# Power_CH340G.net
KiCad netlist of a schematic drawn in Altium Designer
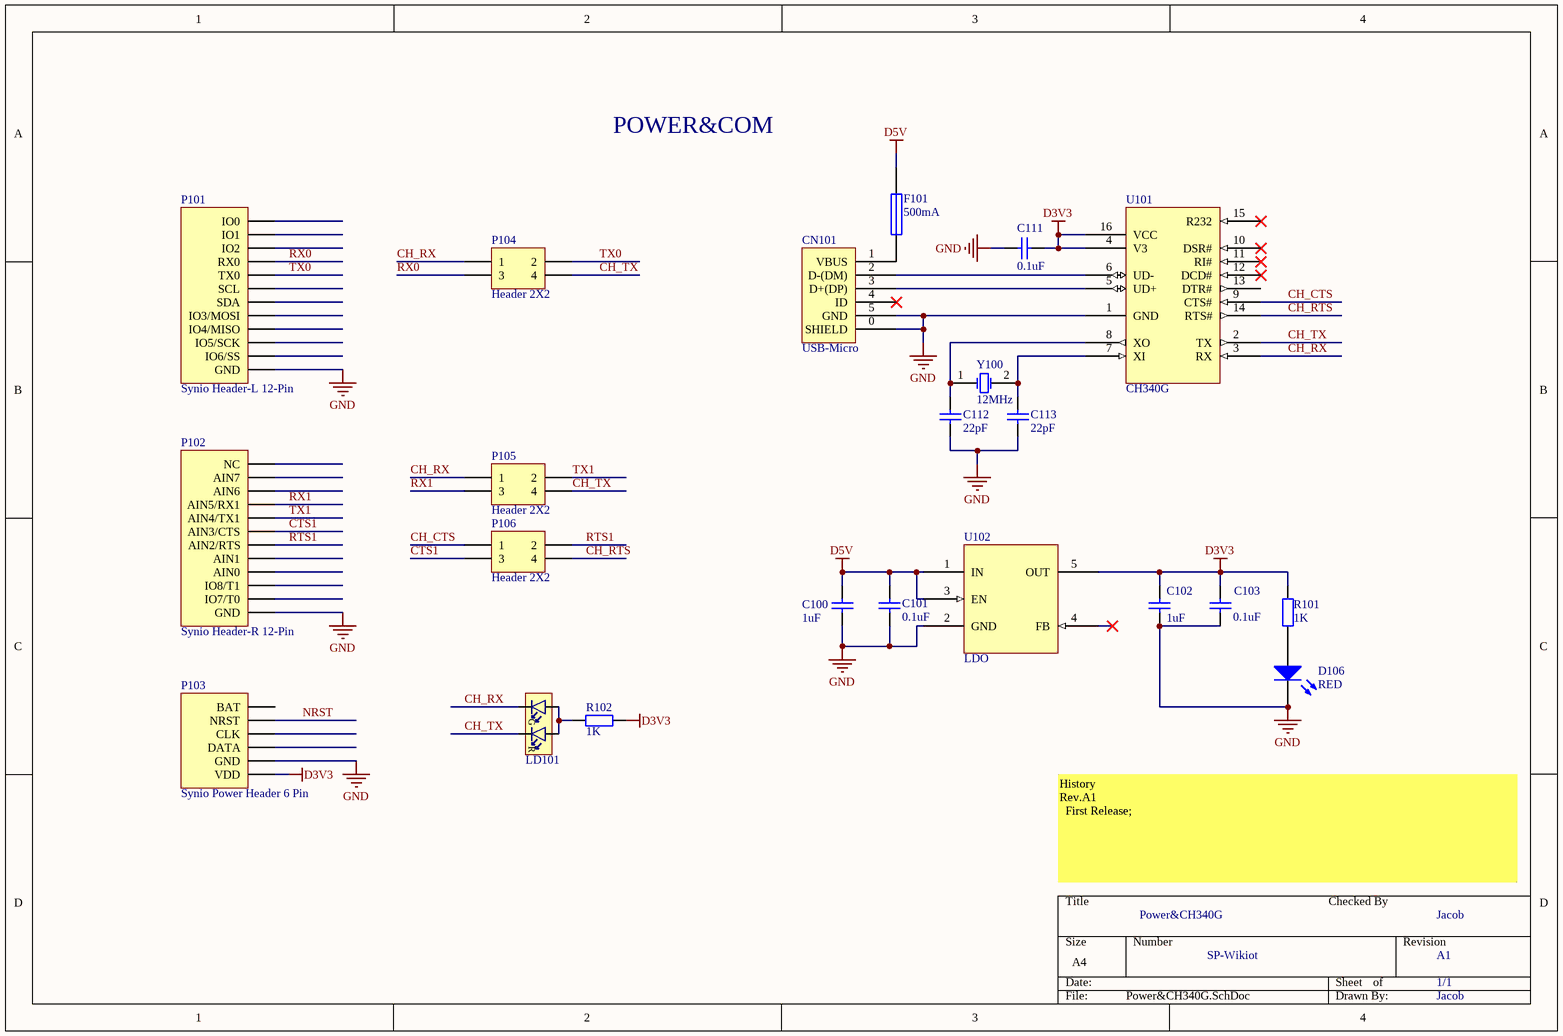
[diagram p0: Power&CH340G.SchDoc]

(export (version "E")
  (design (tool "Eeschema 10.0.6"))
  (components
    (comp (ref "C100")
      (value "1uF")
      (footprint "0603M")
      (description "Capacitor")
      (libsource (lib "Studio") (part "Cap"))
    )
    (comp (ref "C101")
      (value "0.1uF")
      (footprint "0603M")
      (description "Capacitor")
      (libsource (lib "Studio") (part "Cap"))
    )
    (comp (ref "C102")
      (value "1uF")
      (footprint "0603M")
      (description "Capacitor")
      (libsource (lib "Studio") (part "Cap"))
    )
    (comp (ref "C103")
      (value "0.1uF")
      (footprint "0603M")
      (description "Capacitor")
      (libsource (lib "Studio") (part "Cap"))
    )
    (comp (ref "C111")
      (value "0.1uF")
      (footprint "0603M")
      (description "Capacitor")
      (libsource (lib "Studio") (part "Cap"))
    )
    (comp (ref "C112")
      (value "22pF")
      (footprint "0603M")
      (description "Capacitor")
      (fields (field (name "PUBLISHER") "Altium Limited"))
      (libsource (lib "Miscellaneous Devices") (part "Cap"))
    )
    (comp (ref "C113")
      (value "22pF")
      (footprint "0603M")
      (description "Capacitor")
      (fields (field (name "PUBLISHER") "Altium Limited"))
      (libsource (lib "Miscellaneous Devices") (part "Cap"))
    )
    (comp (ref "CN101")
      (value "USB-Micro")
      (footprint "USB-MICRO-Female-Lite")
      (libsource (lib "Connector") (part "USB-Micro"))
    )
    (comp (ref "D106")
      (value "RED")
      (footprint "0603pn")
      (description "Typical INFRARED GaAs LED")
      (fields (field (name "PUBLISHER") "Altium Limited"))
      (libsource (lib "Miscellaneous Devices") (part "LED0"))
    )
    (comp (ref "F101")
      (value "500mA")
      (footprint "0805")
      (description "Fuse")
      (fields (field (name "PUBLISHER") "Altium Limited"))
      (libsource (lib "Studio") (part "Fuse 1"))
    )
    (comp (ref "LD101")
      (value "LTST-C195KGJRKT")
      (footprint "0805-LED-Bi")
      (description "Avago, HSMF-A203 Bi-Color LED")
      (fields
        (field (name "MANUFACTURER") "Lite-On Inc")
        (field (name "2ND SOURCE PART NUMBER") "859-LTST-C195KGJRKT")
        (field (name "PUBLISHER") "Nordic Semiconductor")
      )
      (libsource (lib "Misc") (part "LED-DUAL"))
    )
    (comp (ref "P101")
      (value "Synio Header-L 12-Pin")
      (footprint "HDR1X12")
      (description "Synio Header-L, 12-Pin")
      (fields (field (name "PUBLISHER") "Altium Limited"))
      (libsource (lib "Connector") (part "Synio Header-L 12-Pin"))
    )
    (comp (ref "P102")
      (value "Synio Header-R 12-Pin")
      (footprint "HDR1X12")
      (description "Synio Header-R, 12-Pin")
      (fields (field (name "PUBLISHER") "Altium Limited"))
      (libsource (lib "Connector") (part "Synio Header-R 12-Pin"))
    )
    (comp (ref "P103")
      (value "Synio Power Header 6 Pin")
      (footprint "HDR1X6/2.54MM")
      (libsource (lib "Connector") (part "Synio Power Header 6 Pin"))
    )
    (comp (ref "P104")
      (value "Header 2X2")
      (footprint "HDR2X2/2.54MM")
      (description "Header, 2-Pin, Dual row")
      (fields (field (name "PUBLISHER") "Altium Limited"))
      (libsource (lib "Miscellaneous Connectors") (part "Header 2X2"))
    )
    (comp (ref "P105")
      (value "Header 2X2")
      (footprint "HDR2X2/2.54MM")
      (description "Header, 2-Pin, Dual row")
      (fields (field (name "PUBLISHER") "Altium Limited"))
      (libsource (lib "Miscellaneous Connectors") (part "Header 2X2"))
    )
    (comp (ref "P106")
      (value "Header 2X2")
      (footprint "HDR2X2/2.54MM")
      (description "Header, 2-Pin, Dual row")
      (fields (field (name "PUBLISHER") "Altium Limited"))
      (libsource (lib "Miscellaneous Connectors") (part "Header 2X2"))
    )
    (comp (ref "R101")
      (value "1K")
      (footprint "0603M")
      (description "Resistor")
      (fields (field (name "PUBLISHER") "Altium Limited"))
      (libsource (lib "") (part "Res2_1"))
    )
    (comp (ref "R102")
      (value "1K")
      (footprint "0603M")
      (description "Resistor")
      (fields (field (name "PUBLISHER") "Altium Limited"))
      (libsource (lib "Miscellaneous Devices") (part "Res2"))
    )
    (comp (ref "U101")
      (value "CH340G")
      (footprint "SO16_M")
      (description "USB to UART IC")
      (libsource (lib "Logic") (part "CH340G"))
    )
    (comp (ref "U102")
      (value "LDO")
      (footprint "SOT23-5")
      (description "General LDO SOT23-5")
      (libsource (lib "Power") (part "LDO-SOT23-5"))
    )
    (comp (ref "Y100")
      (value "12MHz")
      (footprint "XTAL_49S")
      (description "Crystal Oscillator")
      (fields (field (name "PUBLISHER") "Altium Limited"))
      (libsource (lib "Miscellaneous Devices") (part "XTAL"))
    )
  )
  (nets
    (net (code "1") (name "/CH_CTS") (class "Default")
      (node (ref "P106") (pin "1") (pinfunction "1_1") (pintype "passive"))
      (node (ref "U101") (pin "9") (pinfunction "CTS#_9") (pintype "input"))
    )
    (net (code "2") (name "/CH_RTS") (class "Default")
      (node (ref "P106") (pin "4") (pinfunction "4_4") (pintype "passive"))
      (node (ref "U101") (pin "14") (pinfunction "RTS#_14") (pintype "output"))
    )
    (net (code "3") (name "/CH_RX") (class "Default")
      (node (ref "LD101") (pin "1") (pinfunction "C1_1") (pintype "passive"))
      (node (ref "P104") (pin "1") (pinfunction "1_1") (pintype "passive"))
      (node (ref "P105") (pin "1") (pinfunction "1_1") (pintype "passive"))
      (node (ref "U101") (pin "3") (pinfunction "RX_3") (pintype "input"))
    )
    (net (code "4") (name "/CH_TX") (class "Default")
      (node (ref "LD101") (pin "2") (pinfunction "C2_2") (pintype "passive"))
      (node (ref "P104") (pin "4") (pinfunction "4_4") (pintype "passive"))
      (node (ref "P105") (pin "4") (pinfunction "4_4") (pintype "passive"))
      (node (ref "U101") (pin "2") (pinfunction "TX_2") (pintype "output"))
    )
    (net (code "5") (name "/CTS1") (class "Default")
      (node (ref "P102") (pin "7") (pinfunction "AIN3/CTS_7") (pintype "passive"))
      (node (ref "P106") (pin "3") (pinfunction "3_3") (pintype "passive"))
    )
    (net (code "6") (name "/NRST") (class "Default")
      (node (ref "P103") (pin "5") (pinfunction "NRST_5") (pintype "passive"))
    )
    (net (code "7") (name "/RTS1") (class "Default")
      (node (ref "P102") (pin "6") (pinfunction "AIN2/RTS_6") (pintype "passive"))
      (node (ref "P106") (pin "2") (pinfunction "2_2") (pintype "passive"))
    )
    (net (code "8") (name "/RX0") (class "Default")
      (node (ref "P101") (pin "9") (pinfunction "RX0_9") (pintype "passive"))
      (node (ref "P104") (pin "3") (pinfunction "3_3") (pintype "passive"))
    )
    (net (code "9") (name "/RX1") (class "Default")
      (node (ref "P102") (pin "9") (pinfunction "AIN5/RX1_9") (pintype "passive"))
      (node (ref "P105") (pin "3") (pinfunction "3_3") (pintype "passive"))
    )
    (net (code "10") (name "/TX0") (class "Default")
      (node (ref "P101") (pin "8") (pinfunction "TX0_8") (pintype "passive"))
      (node (ref "P104") (pin "2") (pinfunction "2_2") (pintype "passive"))
    )
    (net (code "11") (name "/TX1") (class "Default")
      (node (ref "P102") (pin "8") (pinfunction "AIN4/TX1_8") (pintype "passive"))
      (node (ref "P105") (pin "2") (pinfunction "2_2") (pintype "passive"))
    )
    (net (code "12") (name "D3V3") (class "Default")
      (node (ref "C102") (pin "2") (pinfunction "2_2") (pintype "passive"))
      (node (ref "C103") (pin "2") (pinfunction "2_2") (pintype "passive"))
      (node (ref "C111") (pin "2") (pinfunction "2_2") (pintype "passive"))
      (node (ref "P103") (pin "1") (pinfunction "VDD_1") (pintype "passive"))
      (node (ref "R101") (pin "2") (pinfunction "2_2") (pintype "passive"))
      (node (ref "R102") (pin "1") (pinfunction "1_1") (pintype "passive"))
      (node (ref "U101") (pin "16") (pinfunction "VCC_16") (pintype "power_in"))
      (node (ref "U101") (pin "4") (pinfunction "V3_4") (pintype "power_in"))
      (node (ref "U102") (pin "5") (pinfunction "OUT_5") (pintype "power_in"))
    )
    (net (code "13") (name "D5V") (class "Default")
      (node (ref "C100") (pin "2") (pinfunction "2_2") (pintype "passive"))
      (node (ref "C101") (pin "2") (pinfunction "2_2") (pintype "passive"))
      (node (ref "F101") (pin "1") (pinfunction "1_1") (pintype "passive"))
      (node (ref "U102") (pin "1") (pinfunction "IN_1") (pintype "power_in"))
      (node (ref "U102") (pin "3") (pinfunction "EN_3") (pintype "input"))
    )
    (net (code "14") (name "GND") (class "Default")
      (node (ref "C100") (pin "1") (pinfunction "1_1") (pintype "passive"))
      (node (ref "C101") (pin "1") (pinfunction "1_1") (pintype "passive"))
      (node (ref "C102") (pin "1") (pinfunction "1_1") (pintype "passive"))
      (node (ref "C103") (pin "1") (pinfunction "1_1") (pintype "passive"))
      (node (ref "C111") (pin "1") (pinfunction "1_1") (pintype "passive"))
      (node (ref "C112") (pin "1") (pinfunction "1_1") (pintype "passive"))
      (node (ref "C113") (pin "1") (pinfunction "1_1") (pintype "passive"))
      (node (ref "CN101") (pin "0") (pinfunction "SHIELD_0") (pintype "passive"))
      (node (ref "CN101") (pin "5") (pinfunction "GND_5") (pintype "passive"))
      (node (ref "D106") (pin "2") (pinfunction "K_2") (pintype "passive"))
      (node (ref "P101") (pin "1") (pinfunction "GND_1") (pintype "passive"))
      (node (ref "P102") (pin "1") (pinfunction "GND_1") (pintype "passive"))
      (node (ref "P103") (pin "2") (pinfunction "GND_2") (pintype "passive"))
      (node (ref "U101") (pin "1") (pinfunction "GND_1") (pintype "power_in"))
      (node (ref "U102") (pin "2") (pinfunction "GND_2") (pintype "power_in"))
    )
    (net (code "15") (name "Net-(CN101-D+(DP))") (class "Default")
      (node (ref "CN101") (pin "3") (pinfunction "D+(DP)_3") (pintype "passive"))
      (node (ref "U101") (pin "5") (pinfunction "UD+_5") (pintype "bidirectional"))
    )
    (net (code "16") (name "Net-(CN101-D-(DM))") (class "Default")
      (node (ref "CN101") (pin "2") (pinfunction "D-(DM)_2") (pintype "passive"))
      (node (ref "U101") (pin "6") (pinfunction "UD-_6") (pintype "bidirectional"))
    )
    (net (code "17") (name "Net-(CN101-VBUS)") (class "Default")
      (node (ref "CN101") (pin "1") (pinfunction "VBUS_1") (pintype "passive"))
      (node (ref "F101") (pin "2") (pinfunction "2_2") (pintype "passive"))
    )
    (net (code "18") (name "Net-(D106-A)") (class "Default")
      (node (ref "D106") (pin "1") (pinfunction "A_1") (pintype "passive"))
      (node (ref "R101") (pin "1") (pinfunction "1_1") (pintype "passive"))
    )
    (net (code "19") (name "Net-(LD101-A1)") (class "Default")
      (node (ref "LD101") (pin "3") (pinfunction "A2_3") (pintype "passive"))
      (node (ref "LD101") (pin "4") (pinfunction "A1_4") (pintype "passive"))
      (node (ref "R102") (pin "2") (pinfunction "2_2") (pintype "passive"))
    )
    (net (code "20") (name "Net-(U101-XI)") (class "Default")
      (node (ref "C113") (pin "2") (pinfunction "2_2") (pintype "passive"))
      (node (ref "U101") (pin "7") (pinfunction "XI_7") (pintype "input"))
      (node (ref "Y100") (pin "2") (pinfunction "OSC2_2") (pintype "passive"))
    )
    (net (code "21") (name "Net-(U101-XO)") (class "Default")
      (node (ref "C112") (pin "2") (pinfunction "2_2") (pintype "passive"))
      (node (ref "U101") (pin "8") (pinfunction "XO_8") (pintype "output"))
      (node (ref "Y100") (pin "1") (pinfunction "OSC1_1") (pintype "passive"))
    )
    (net (code "22") (name "unconnected-(CN101-ID-Pad4)") (class "Default")
      (node (ref "CN101") (pin "4") (pinfunction "ID_4") (pintype "passive+no_connect"))
    )
    (net (code "23") (name "unconnected-(P101-IO0-Pad12)") (class "Default")
      (node (ref "P101") (pin "12") (pinfunction "IO0_12") (pintype "passive"))
    )
    (net (code "24") (name "unconnected-(P101-IO1-Pad11)") (class "Default")
      (node (ref "P101") (pin "11") (pinfunction "IO1_11") (pintype "passive"))
    )
    (net (code "25") (name "unconnected-(P101-IO2-Pad10)") (class "Default")
      (node (ref "P101") (pin "10") (pinfunction "IO2_10") (pintype "passive"))
    )
    (net (code "26") (name "unconnected-(P101-IO3{slash}MOSI-Pad5)") (class "Default")
      (node (ref "P101") (pin "5") (pinfunction "IO3/MOSI_5") (pintype "passive"))
    )
    (net (code "27") (name "unconnected-(P101-IO4{slash}MISO-Pad4)") (class "Default")
      (node (ref "P101") (pin "4") (pinfunction "IO4/MISO_4") (pintype "passive"))
    )
    (net (code "28") (name "unconnected-(P101-IO5{slash}SCK-Pad3)") (class "Default")
      (node (ref "P101") (pin "3") (pinfunction "IO5/SCK_3") (pintype "passive"))
    )
    (net (code "29") (name "unconnected-(P101-IO6{slash}SS-Pad2)") (class "Default")
      (node (ref "P101") (pin "2") (pinfunction "IO6/SS_2") (pintype "passive"))
    )
    (net (code "30") (name "unconnected-(P101-SCL-Pad7)") (class "Default")
      (node (ref "P101") (pin "7") (pinfunction "SCL_7") (pintype "passive"))
    )
    (net (code "31") (name "unconnected-(P101-SDA-Pad6)") (class "Default")
      (node (ref "P101") (pin "6") (pinfunction "SDA_6") (pintype "passive"))
    )
    (net (code "32") (name "unconnected-(P102-AIN0-Pad4)") (class "Default")
      (node (ref "P102") (pin "4") (pinfunction "AIN0_4") (pintype "passive"))
    )
    (net (code "33") (name "unconnected-(P102-AIN1-Pad5)") (class "Default")
      (node (ref "P102") (pin "5") (pinfunction "AIN1_5") (pintype "passive"))
    )
    (net (code "34") (name "unconnected-(P102-AIN6-Pad10)") (class "Default")
      (node (ref "P102") (pin "10") (pinfunction "AIN6_10") (pintype "passive"))
    )
    (net (code "35") (name "unconnected-(P102-AIN7-Pad11)") (class "Default")
      (node (ref "P102") (pin "11") (pinfunction "AIN7_11") (pintype "passive"))
    )
    (net (code "36") (name "unconnected-(P102-IO7{slash}T0-Pad2)") (class "Default")
      (node (ref "P102") (pin "2") (pinfunction "IO7/T0_2") (pintype "passive"))
    )
    (net (code "37") (name "unconnected-(P102-IO8{slash}T1-Pad3)") (class "Default")
      (node (ref "P102") (pin "3") (pinfunction "IO8/T1_3") (pintype "passive"))
    )
    (net (code "38") (name "unconnected-(P102-NC-Pad12)") (class "Default")
      (node (ref "P102") (pin "12") (pinfunction "NC_12") (pintype "passive"))
    )
    (net (code "39") (name "unconnected-(P103-BAT-Pad6)") (class "Default")
      (node (ref "P103") (pin "6") (pinfunction "BAT_6") (pintype "passive"))
    )
    (net (code "40") (name "unconnected-(P103-CLK-Pad4)") (class "Default")
      (node (ref "P103") (pin "4") (pinfunction "CLK_4") (pintype "passive"))
    )
    (net (code "41") (name "unconnected-(P103-DATA-Pad3)") (class "Default")
      (node (ref "P103") (pin "3") (pinfunction "DATA_3") (pintype "passive"))
    )
    (net (code "42") (name "unconnected-(U101-DCD#-Pad12)") (class "Default")
      (node (ref "U101") (pin "12") (pinfunction "DCD#_12") (pintype "input+no_connect"))
    )
    (net (code "43") (name "unconnected-(U101-DSR#-Pad10)") (class "Default")
      (node (ref "U101") (pin "10") (pinfunction "DSR#_10") (pintype "input+no_connect"))
    )
    (net (code "44") (name "unconnected-(U101-DTR#-Pad13)") (class "Default")
      (node (ref "U101") (pin "13") (pinfunction "DTR#_13") (pintype "output"))
    )
    (net (code "45") (name "unconnected-(U101-R232-Pad15)") (class "Default")
      (node (ref "U101") (pin "15") (pinfunction "R232_15") (pintype "input+no_connect"))
    )
    (net (code "46") (name "unconnected-(U101-RI#-Pad11)") (class "Default")
      (node (ref "U101") (pin "11") (pinfunction "RI#_11") (pintype "input+no_connect"))
    )
    (net (code "47") (name "unconnected-(U102-FB-Pad4)") (class "Default")
      (node (ref "U102") (pin "4") (pinfunction "FB_4") (pintype "input+no_connect"))
    )
  )
)
